# PhatStats_Slim_Enclosure_ESP_Lolin_D32_X.net
KiCad netlist of a schematic drawn in EAGLE
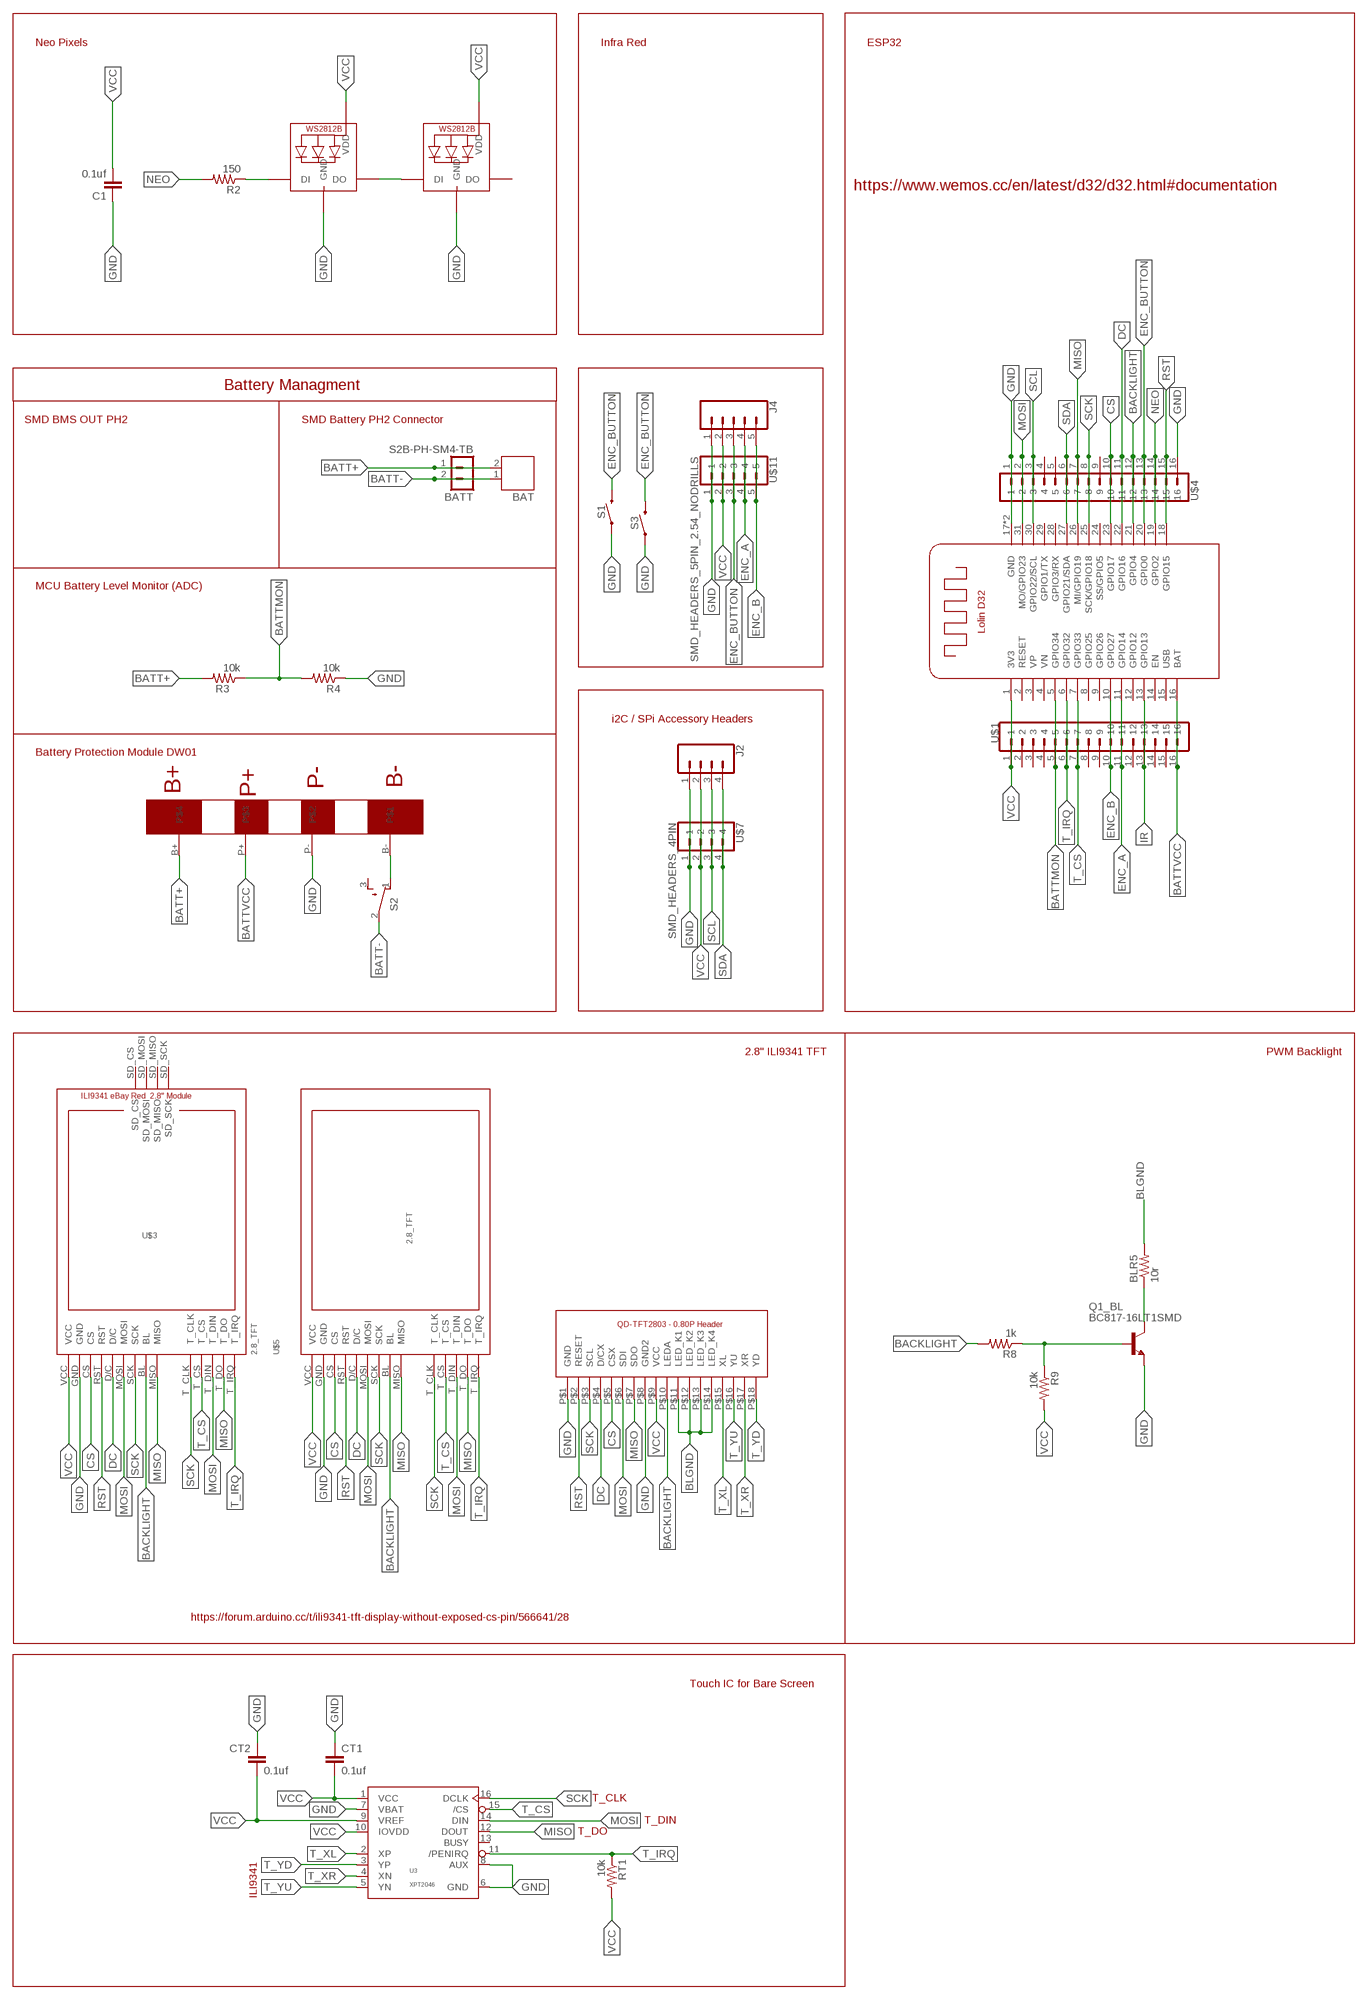
[diagram p0: schematic, sheet 1]

(export (version "E")
  (design (tool "Eeschema 10.0.6"))
  (components
    (comp (ref "0")
      (value "ILI9341-2.8")
      (footprint "eagle-import:ILI9341-2.8")
      (libsource (lib "eagle-import") (part "ILI9341-2.8"))
    )
    (comp (ref "BAT")
      (value "JST-PH2")
      (footprint "eagle-import:JST-PH2")
      (libsource (lib "eagle-import") (part "JST-PH2"))
    )
    (comp (ref "BATT")
      (value "S2B-PH-SM4-TB")
      (footprint "eagle-import:S2B-PH-SM4-TB")
      (libsource (lib "eagle-import") (part "S2B-PH-SM4-TB"))
    )
    (comp (ref "BLR5")
      (value "10r")
      (footprint "eagle-import:M1206")
      (libsource (lib "eagle-import") (part "R-US_M1206"))
    )
    (comp (ref "BMS")
      (value "DW01BATTERYPROT")
      (footprint "eagle-import:DW01BATTERYPROT")
      (libsource (lib "eagle-import") (part "DW01BATTERYPROT"))
    )
    (comp (ref "C1")
      (value "0.1uf")
      (footprint "eagle-import:C1206")
      (libsource (lib "eagle-import") (part "C-EUC1206"))
    )
    (comp (ref "CT1")
      (value "0.1uf")
      (footprint "eagle-import:C1206")
      (libsource (lib "eagle-import") (part "C-EUC1206"))
    )
    (comp (ref "CT2")
      (value "0.1uf")
      (footprint "eagle-import:C1206")
      (libsource (lib "eagle-import") (part "C-EUC1206"))
    )
    (comp (ref "J2")
      (value "CONN_04PTH")
      (footprint "eagle-import:1X04")
      (libsource (lib "eagle-import") (part "CONN_04PTH"))
    )
    (comp (ref "J4")
      (value "CONN_05")
      (footprint "eagle-import:1X05")
      (libsource (lib "eagle-import") (part "CONN_05"))
    )
    (comp (ref "NEO0")
      (value "WS2812B5050")
      (footprint "eagle-import:WS2812B")
      (libsource (lib "eagle-import") (part "WS2812B5050"))
    )
    (comp (ref "NEO1")
      (value "WS2812B5050")
      (footprint "eagle-import:WS2812B")
      (libsource (lib "eagle-import") (part "WS2812B5050"))
    )
    (comp (ref "Q1_BL")
      (value "BC817-16LT1SMD")
      (footprint "eagle-import:SOT23-BEC")
      (libsource (lib "eagle-import") (part "BC817SMD-16LT1"))
    )
    (comp (ref "R2")
      (value "150")
      (footprint "eagle-import:M1206")
      (libsource (lib "eagle-import") (part "R-US_M1206"))
    )
    (comp (ref "R3")
      (value "10k")
      (footprint "eagle-import:M1206")
      (libsource (lib "eagle-import") (part "R-US_M1206"))
    )
    (comp (ref "R4")
      (value "10k")
      (footprint "eagle-import:M1206")
      (libsource (lib "eagle-import") (part "R-US_M1206"))
    )
    (comp (ref "R8")
      (value "1k")
      (footprint "eagle-import:M1206")
      (libsource (lib "eagle-import") (part "R-US_M1206"))
    )
    (comp (ref "R9")
      (value "10k")
      (footprint "eagle-import:M1206")
      (libsource (lib "eagle-import") (part "R-US_M1206"))
    )
    (comp (ref "RT1")
      (value "10k")
      (footprint "eagle-import:M1206")
      (libsource (lib "eagle-import") (part "R-US_M1206"))
    )
    (comp (ref "S1")
      (value "MOMENTARY-SWITCH-SPST-PTH-6.0MM")
      (footprint "eagle-import:TACTILE_SWITCH_PTH_6.0MM")
      (libsource (lib "eagle-import") (part "MOMENTARY-SWITCH-SPST-PTH-6.0MM"))
    )
    (comp (ref "S2")
      (value "SK-12F14(1P2T)0.5A50VDC3MMPITCH")
      (footprint "eagle-import:SK-12F14(1P2T)0.5A50VDC3MMPITCH")
      (libsource (lib "eagle-import") (part "SK-12F14(1P2T)0.5A50VDC3MMPITCH"))
    )
    (comp (ref "S3")
      (value "MOMENTARY-SWITCH-SPST-SMD-6.2MM-TALL")
      (footprint "eagle-import:TACTILE_SWITCH_SMD_6.2MM_TALL")
      (libsource (lib "eagle-import") (part "MOMENTARY-SWITCH-SPST-SMD-6.2MM-TALL"))
    )
    (comp (ref "U$1")
      (value "SMD_HEADERS_16PIN_2.54_NODRILLSSMD_HEADERS_16PIN")
      (footprint "eagle-import:SMD_HEADERS_16PIN")
      (libsource (lib "eagle-import") (part "SMD_HEADERS_16PIN_2.54_NODRILLSSMD_HEADERS_16PIN"))
    )
    (comp (ref "U$2")
      (value "TML_LOLIND32")
      (footprint "eagle-import:TML_LOLIND32")
      (libsource (lib "eagle-import") (part "TML_LOLIND32"))
    )
    (comp (ref "U$3")
      (value "2.8_TFT")
      (footprint "eagle-import:2.8_TFT")
      (libsource (lib "eagle-import") (part "2.8_TFT"))
    )
    (comp (ref "U$4")
      (value "SMD_HEADERS_16PIN_2.54_NODRILLSSMD_HEADERS_16PIN")
      (footprint "eagle-import:SMD_HEADERS_16PIN")
      (libsource (lib "eagle-import") (part "SMD_HEADERS_16PIN_2.54_NODRILLSSMD_HEADERS_16PIN"))
    )
    (comp (ref "U$5")
      (value "2.8_TFT")
      (footprint "eagle-import:2.8_TFT")
      (libsource (lib "eagle-import") (part "TML_ili9341-2.8_tft-display_PinHeader only_2.8_TFT"))
    )
    (comp (ref "U$7")
      (value "SMD_HEADERS_4PIN")
      (footprint "eagle-import:SMD_HEADERS_4PIN")
      (libsource (lib "eagle-import") (part "SMD_HEADERS_4PIN"))
    )
    (comp (ref "U$11")
      (value "SMD_HEADERS_5PIN_2.54_NODRILLS")
      (footprint "eagle-import:SMD_HEADERS_5PIN")
      (libsource (lib "eagle-import") (part "SMD_HEADERS_5PIN_2.54_NODRILLS"))
    )
    (comp (ref "U3")
      (value "XPT2046")
      (footprint "eagle-import:TSSOP-16")
      (fields (field (name "MF") "Xptek"))
      (libsource (lib "eagle-import") (part "XPT2046"))
    )
  )
  (nets
    (net (code "1") (name "/USB") (class "Default")
      (node (ref "U$2") (pin "15") (pinfunction "USB_15") (pintype "power_in"))
    )
    (net (code "2") (name "BACKLIGHT") (class "Default")
      (node (ref "0") (pin "P$10") (pinfunction "LEDA_P$10") (pintype "bidirectional"))
      (node (ref "R8") (pin "2") (pinfunction "2_2") (pintype "passive"))
      (node (ref "U$2") (pin "21") (pinfunction "GPIO4_21") (pintype "bidirectional"))
      (node (ref "U$3") (pin "BL") (pinfunction "BL_BL") (pintype "bidirectional"))
      (node (ref "U$4") (pin "12") (pinfunction "12_12") (pintype "passive"))
      (node (ref "U$5") (pin "BL") (pinfunction "BL_BL") (pintype "bidirectional"))
    )
    (net (code "3") (name "BATT+") (class "Default")
      (node (ref "BAT") (pin "2") (pinfunction "2_2") (pintype "passive"))
      (node (ref "BATT") (pin "1") (pinfunction "1_1") (pintype "passive"))
      (node (ref "BMS") (pin "B+") (pinfunction "P$4_B+") (pintype "bidirectional"))
      (node (ref "R3") (pin "2") (pinfunction "2_2") (pintype "passive"))
    )
    (net (code "4") (name "BATT-") (class "Default")
      (node (ref "BAT") (pin "1") (pinfunction "1_1") (pintype "passive"))
      (node (ref "BATT") (pin "2") (pinfunction "2_2") (pintype "passive"))
      (node (ref "S2") (pin "2") (pinfunction "P_2") (pintype "passive"))
    )
    (net (code "5") (name "BATTMON") (class "Default")
      (node (ref "R3") (pin "1") (pinfunction "1_1") (pintype "passive"))
      (node (ref "R4") (pin "2") (pinfunction "2_2") (pintype "passive"))
      (node (ref "U$1") (pin "5") (pinfunction "5_5") (pintype "passive"))
      (node (ref "U$2") (pin "5") (pinfunction "GPIO34_5") (pintype "input"))
    )
    (net (code "6") (name "BATTVCC") (class "Default")
      (node (ref "BMS") (pin "P+") (pinfunction "P$3_P+") (pintype "bidirectional"))
      (node (ref "U$1") (pin "16") (pinfunction "16_16") (pintype "passive"))
      (node (ref "U$2") (pin "16") (pinfunction "BAT_16") (pintype "power_in"))
    )
    (net (code "7") (name "BLGND") (class "Default")
      (node (ref "0") (pin "P$11") (pinfunction "LED_K1_P$11") (pintype "bidirectional"))
      (node (ref "0") (pin "P$12") (pinfunction "LED_K2_P$12") (pintype "bidirectional"))
      (node (ref "0") (pin "P$13") (pinfunction "LED_K3_P$13") (pintype "bidirectional"))
      (node (ref "0") (pin "P$14") (pinfunction "LED_K4_P$14") (pintype "bidirectional"))
      (node (ref "BLR5") (pin "2") (pinfunction "2_2") (pintype "passive"))
    )
    (net (code "8") (name "CS") (class "Default")
      (node (ref "0") (pin "P$5") (pinfunction "CSX_P$5") (pintype "bidirectional"))
      (node (ref "U$2") (pin "23") (pinfunction "GPIO17_23") (pintype "bidirectional"))
      (node (ref "U$3") (pin "CS") (pinfunction "CS_CS") (pintype "bidirectional"))
      (node (ref "U$4") (pin "10") (pinfunction "10_10") (pintype "passive"))
      (node (ref "U$5") (pin "CS") (pinfunction "CS_CS") (pintype "bidirectional"))
    )
    (net (code "9") (name "DC") (class "Default")
      (node (ref "0") (pin "P$4") (pinfunction "D/CX_P$4") (pintype "bidirectional"))
      (node (ref "U$2") (pin "22") (pinfunction "GPIO16_22") (pintype "bidirectional"))
      (node (ref "U$3") (pin "D/C") (pinfunction "D/C_D/C") (pintype "bidirectional"))
      (node (ref "U$4") (pin "11") (pinfunction "11_11") (pintype "passive"))
      (node (ref "U$5") (pin "D/C") (pinfunction "D/C_D/C") (pintype "bidirectional"))
    )
    (net (code "10") (name "ENC_A") (class "Default")
      (node (ref "J4") (pin "4") (pinfunction "4_4") (pintype "passive"))
      (node (ref "U$1") (pin "11") (pinfunction "11_11") (pintype "passive"))
      (node (ref "U$11") (pin "4") (pinfunction "4_4") (pintype "passive"))
      (node (ref "U$2") (pin "11") (pinfunction "GPIO14_11") (pintype "bidirectional"))
    )
    (net (code "11") (name "ENC_B") (class "Default")
      (node (ref "J4") (pin "5") (pinfunction "5_5") (pintype "passive"))
      (node (ref "U$1") (pin "10") (pinfunction "10_10") (pintype "passive"))
      (node (ref "U$11") (pin "5") (pinfunction "5_5") (pintype "passive"))
      (node (ref "U$2") (pin "10") (pinfunction "GPIO27_10") (pintype "bidirectional"))
    )
    (net (code "12") (name "ENC_BUTTON") (class "Default")
      (node (ref "J4") (pin "3") (pinfunction "3_3") (pintype "passive"))
      (node (ref "S1") (pin "3") (pinfunction "2_3") (pintype "passive"))
      (node (ref "S3") (pin "B2") (pinfunction "2_B2") (pintype "passive"))
      (node (ref "U$11") (pin "3") (pinfunction "3_3") (pintype "passive"))
      (node (ref "U$2") (pin "20") (pinfunction "GPIO0_20") (pintype "bidirectional"))
      (node (ref "U$4") (pin "13") (pinfunction "13_13") (pintype "passive"))
    )
    (net (code "13") (name "GND") (class "Default")
      (node (ref "0") (pin "P$1") (pinfunction "GND_P$1") (pintype "bidirectional"))
      (node (ref "0") (pin "P$8") (pinfunction "GND2_P$8") (pintype "bidirectional"))
      (node (ref "BMS") (pin "P-") (pinfunction "P$2_P-") (pintype "bidirectional"))
      (node (ref "C1") (pin "1") (pinfunction "1_1") (pintype "passive"))
      (node (ref "CT1") (pin "1") (pinfunction "1_1") (pintype "passive"))
      (node (ref "CT2") (pin "1") (pinfunction "1_1") (pintype "passive"))
      (node (ref "J2") (pin "1") (pinfunction "1_1") (pintype "passive"))
      (node (ref "J4") (pin "1") (pinfunction "1_1") (pintype "passive"))
      (node (ref "NEO0") (pin "3-GND") (pinfunction "GND_3-GND") (pintype "power_in"))
      (node (ref "NEO1") (pin "3-GND") (pinfunction "GND_3-GND") (pintype "power_in"))
      (node (ref "Q1_BL") (pin "E") (pinfunction "E_E") (pintype "passive"))
      (node (ref "R4") (pin "1") (pinfunction "1_1") (pintype "passive"))
      (node (ref "S1") (pin "1") (pinfunction "1_1") (pintype "passive"))
      (node (ref "S3") (pin "A2") (pinfunction "1_A2") (pintype "passive"))
      (node (ref "U$11") (pin "1") (pinfunction "1_1") (pintype "passive"))
      (node (ref "U$2") (pin "17") (pinfunction "GND_17") (pintype "power_in"))
      (node (ref "U$2") (pin "32") (pinfunction "GND_32") (pintype "power_in"))
      (node (ref "U$3") (pin "GND") (pinfunction "GND_GND") (pintype "bidirectional"))
      (node (ref "U$4") (pin "1") (pinfunction "1_1") (pintype "passive"))
      (node (ref "U$4") (pin "16") (pinfunction "16_16") (pintype "passive"))
      (node (ref "U$5") (pin "GND") (pinfunction "GND_GND") (pintype "bidirectional"))
      (node (ref "U$7") (pin "1") (pinfunction "1_1") (pintype "passive"))
      (node (ref "U3") (pin "6") (pinfunction "GND_6") (pintype "power_in"))
      (node (ref "U3") (pin "7") (pinfunction "VBAT_7") (pintype "input"))
      (node (ref "U3") (pin "8") (pinfunction "AUX_8") (pintype "input"))
    )
    (net (code "14") (name "IR") (class "Default")
      (node (ref "U$1") (pin "13") (pinfunction "13_13") (pintype "passive"))
      (node (ref "U$2") (pin "13") (pinfunction "GPIO13_13") (pintype "bidirectional"))
    )
    (net (code "15") (name "MISO") (class "Default")
      (node (ref "0") (pin "P$7") (pinfunction "SDO_P$7") (pintype "bidirectional"))
      (node (ref "U$2") (pin "26") (pinfunction "MI/GPIO19_26") (pintype "bidirectional"))
      (node (ref "U$3") (pin "MISO") (pinfunction "MISO_MISO") (pintype "bidirectional"))
      (node (ref "U$3") (pin "T_DO") (pinfunction "T_DO_T_DO") (pintype "bidirectional"))
      (node (ref "U$4") (pin "7") (pinfunction "7_7") (pintype "passive"))
      (node (ref "U$5") (pin "MISO") (pinfunction "MISO_MISO") (pintype "bidirectional"))
      (node (ref "U$5") (pin "T_DO") (pinfunction "T_DO_T_DO") (pintype "bidirectional"))
      (node (ref "U3") (pin "12") (pinfunction "DOUT_12") (pintype "output"))
    )
    (net (code "16") (name "MOSI") (class "Default")
      (node (ref "0") (pin "P$6") (pinfunction "SDI_P$6") (pintype "bidirectional"))
      (node (ref "U$2") (pin "31") (pinfunction "MO/GPIO23_31") (pintype "bidirectional"))
      (node (ref "U$3") (pin "MOSI") (pinfunction "MOSI_MOSI") (pintype "bidirectional"))
      (node (ref "U$3") (pin "T_DIN") (pinfunction "T_DIN_T_DIN") (pintype "bidirectional"))
      (node (ref "U$4") (pin "2") (pinfunction "2_2") (pintype "passive"))
      (node (ref "U$5") (pin "MOSI") (pinfunction "MOSI_MOSI") (pintype "bidirectional"))
      (node (ref "U$5") (pin "T_DIN") (pinfunction "T_DIN_T_DIN") (pintype "bidirectional"))
      (node (ref "U3") (pin "14") (pinfunction "DIN_14") (pintype "input"))
    )
    (net (code "17") (name "NEO") (class "Default")
      (node (ref "R2") (pin "2") (pinfunction "2_2") (pintype "passive"))
      (node (ref "U$2") (pin "19") (pinfunction "GPIO2_19") (pintype "bidirectional"))
      (node (ref "U$4") (pin "14") (pinfunction "14_14") (pintype "passive"))
    )
    (net (code "18") (name "Net-(BLR5-Pad1)") (class "Default")
      (node (ref "BLR5") (pin "1") (pinfunction "1_1") (pintype "passive"))
      (node (ref "Q1_BL") (pin "C") (pinfunction "C_C") (pintype "passive"))
    )
    (net (code "19") (name "Net-(BMS-P$1)") (class "Default")
      (node (ref "BMS") (pin "B-") (pinfunction "P$1_B-") (pintype "bidirectional"))
      (node (ref "S2") (pin "1") (pinfunction "O_1") (pintype "passive"))
    )
    (net (code "20") (name "Net-(NEO0-DI)") (class "Default")
      (node (ref "NEO0") (pin "4-DIN") (pinfunction "DI_4-DIN") (pintype "input"))
      (node (ref "R2") (pin "1") (pinfunction "1_1") (pintype "passive"))
    )
    (net (code "21") (name "Net-(NEO0-DO)") (class "Default")
      (node (ref "NEO0") (pin "2-DOUT") (pinfunction "DO_2-DOUT") (pintype "output"))
      (node (ref "NEO1") (pin "4-DIN") (pinfunction "DI_4-DIN") (pintype "input"))
    )
    (net (code "22") (name "Net-(Q1_BL-PadB)") (class "Default")
      (node (ref "Q1_BL") (pin "B") (pinfunction "B_B") (pintype "passive"))
      (node (ref "R8") (pin "1") (pinfunction "1_1") (pintype "passive"))
      (node (ref "R9") (pin "1") (pinfunction "1_1") (pintype "passive"))
    )
    (net (code "23") (name "RST") (class "Default")
      (node (ref "0") (pin "P$2") (pinfunction "RESET_P$2") (pintype "bidirectional"))
      (node (ref "U$2") (pin "18") (pinfunction "GPIO15_18") (pintype "bidirectional"))
      (node (ref "U$3") (pin "RST") (pinfunction "RST_RST") (pintype "bidirectional"))
      (node (ref "U$4") (pin "15") (pinfunction "15_15") (pintype "passive"))
      (node (ref "U$5") (pin "RST") (pinfunction "RST_RST") (pintype "bidirectional"))
    )
    (net (code "24") (name "SCK") (class "Default")
      (node (ref "0") (pin "P$3") (pinfunction "SCL_P$3") (pintype "bidirectional"))
      (node (ref "U$2") (pin "25") (pinfunction "SCK/GPIO18_25") (pintype "bidirectional"))
      (node (ref "U$3") (pin "SCK") (pinfunction "SCK_SCK") (pintype "bidirectional"))
      (node (ref "U$3") (pin "T_CLK") (pinfunction "T_CLK_T_CLK") (pintype "bidirectional"))
      (node (ref "U$4") (pin "8") (pinfunction "8_8") (pintype "passive"))
      (node (ref "U$5") (pin "SCK") (pinfunction "SCK_SCK") (pintype "bidirectional"))
      (node (ref "U$5") (pin "T_CLK") (pinfunction "T_CLK_T_CLK") (pintype "bidirectional"))
      (node (ref "U3") (pin "16") (pinfunction "DCLK_16") (pintype "input"))
    )
    (net (code "25") (name "SCL") (class "Default")
      (node (ref "J2") (pin "3") (pinfunction "3_3") (pintype "passive"))
      (node (ref "U$2") (pin "30") (pinfunction "GPIO22/SCL_30") (pintype "bidirectional"))
      (node (ref "U$4") (pin "3") (pinfunction "3_3") (pintype "passive"))
      (node (ref "U$7") (pin "3") (pinfunction "3_3") (pintype "passive"))
    )
    (net (code "26") (name "SDA") (class "Default")
      (node (ref "J2") (pin "4") (pinfunction "4_4") (pintype "passive"))
      (node (ref "U$2") (pin "27") (pinfunction "GPIO21/SDA_27") (pintype "bidirectional"))
      (node (ref "U$4") (pin "6") (pinfunction "6_6") (pintype "passive"))
      (node (ref "U$7") (pin "4") (pinfunction "4_4") (pintype "passive"))
    )
    (net (code "27") (name "T_CS") (class "Default")
      (node (ref "U$1") (pin "7") (pinfunction "7_7") (pintype "passive"))
      (node (ref "U$2") (pin "7") (pinfunction "GPIO33_7") (pintype "bidirectional"))
      (node (ref "U$3") (pin "T_CS") (pinfunction "T_CS_T_CS") (pintype "bidirectional"))
      (node (ref "U$5") (pin "T_CS") (pinfunction "T_CS_T_CS") (pintype "bidirectional"))
      (node (ref "U3") (pin "15") (pinfunction "/CS_15") (pintype "input"))
    )
    (net (code "28") (name "T_IRQ") (class "Default")
      (node (ref "RT1") (pin "1") (pinfunction "1_1") (pintype "passive"))
      (node (ref "U$1") (pin "6") (pinfunction "6_6") (pintype "passive"))
      (node (ref "U$2") (pin "6") (pinfunction "GPIO32_6") (pintype "bidirectional"))
      (node (ref "U$3") (pin "T_IRQ") (pinfunction "T_IRQ_T_IRQ") (pintype "bidirectional"))
      (node (ref "U$5") (pin "T_IRQ") (pinfunction "T_IRQ_T_IRQ") (pintype "bidirectional"))
      (node (ref "U3") (pin "11") (pinfunction "/PENIRQ_11") (pintype "output"))
    )
    (net (code "29") (name "T_XL") (class "Default")
      (node (ref "0") (pin "P$15") (pinfunction "XL_P$15") (pintype "bidirectional"))
      (node (ref "U3") (pin "2") (pinfunction "XP_2") (pintype "input"))
    )
    (net (code "30") (name "T_XR") (class "Default")
      (node (ref "0") (pin "P$17") (pinfunction "XR_P$17") (pintype "bidirectional"))
      (node (ref "U3") (pin "4") (pinfunction "XN_4") (pintype "input"))
    )
    (net (code "31") (name "T_YD") (class "Default")
      (node (ref "0") (pin "P$18") (pinfunction "YD_P$18") (pintype "bidirectional"))
      (node (ref "U3") (pin "3") (pinfunction "YP_3") (pintype "input"))
    )
    (net (code "32") (name "T_YU") (class "Default")
      (node (ref "0") (pin "P$16") (pinfunction "YU_P$16") (pintype "bidirectional"))
      (node (ref "U3") (pin "5") (pinfunction "YN_5") (pintype "input"))
    )
    (net (code "33") (name "VCC") (class "Default")
      (node (ref "0") (pin "P$9") (pinfunction "VCC_P$9") (pintype "bidirectional"))
      (node (ref "C1") (pin "2") (pinfunction "2_2") (pintype "passive"))
      (node (ref "CT1") (pin "2") (pinfunction "2_2") (pintype "passive"))
      (node (ref "CT2") (pin "2") (pinfunction "2_2") (pintype "passive"))
      (node (ref "J2") (pin "2") (pinfunction "2_2") (pintype "passive"))
      (node (ref "J4") (pin "2") (pinfunction "2_2") (pintype "passive"))
      (node (ref "NEO0") (pin "1-VDD") (pinfunction "VDD_1-VDD") (pintype "power_in"))
      (node (ref "NEO1") (pin "1-VDD") (pinfunction "VDD_1-VDD") (pintype "power_in"))
      (node (ref "R9") (pin "2") (pinfunction "2_2") (pintype "passive"))
      (node (ref "RT1") (pin "2") (pinfunction "2_2") (pintype "passive"))
      (node (ref "U$1") (pin "1") (pinfunction "1_1") (pintype "passive"))
      (node (ref "U$11") (pin "2") (pinfunction "2_2") (pintype "passive"))
      (node (ref "U$2") (pin "1") (pinfunction "3V3_1") (pintype "power_in"))
      (node (ref "U$3") (pin "VCC") (pinfunction "VCC_VCC") (pintype "bidirectional"))
      (node (ref "U$5") (pin "VCC") (pinfunction "VCC_VCC") (pintype "bidirectional"))
      (node (ref "U$7") (pin "2") (pinfunction "2_2") (pintype "passive"))
      (node (ref "U3") (pin "1") (pinfunction "VCC_1") (pintype "power_in"))
      (node (ref "U3") (pin "10") (pinfunction "IOVDD_10") (pintype "power_in"))
      (node (ref "U3") (pin "9") (pinfunction "VREF_9") (pintype "input"))
    )
    (net (code "34") (name "unconnected-(NEO1-DO-Pad2-DOUT)") (class "Default")
      (node (ref "NEO1") (pin "2-DOUT") (pinfunction "DO_2-DOUT") (pintype "output"))
    )
    (net (code "35") (name "unconnected-(S2-S-Pad3)") (class "Default")
      (node (ref "S2") (pin "3") (pinfunction "S_3") (pintype "passive"))
    )
    (net (code "36") (name "unconnected-(U$1-Pad2)") (class "Default")
      (node (ref "U$1") (pin "2") (pinfunction "2_2") (pintype "passive"))
    )
    (net (code "37") (name "unconnected-(U$1-Pad3)") (class "Default")
      (node (ref "U$1") (pin "3") (pinfunction "3_3") (pintype "passive"))
    )
    (net (code "38") (name "unconnected-(U$1-Pad4)") (class "Default")
      (node (ref "U$1") (pin "4") (pinfunction "4_4") (pintype "passive"))
    )
    (net (code "39") (name "unconnected-(U$1-Pad8)") (class "Default")
      (node (ref "U$1") (pin "8") (pinfunction "8_8") (pintype "passive"))
    )
    (net (code "40") (name "unconnected-(U$1-Pad9)") (class "Default")
      (node (ref "U$1") (pin "9") (pinfunction "9_9") (pintype "passive"))
    )
    (net (code "41") (name "unconnected-(U$1-Pad12)") (class "Default")
      (node (ref "U$1") (pin "12") (pinfunction "12_12") (pintype "passive"))
    )
    (net (code "42") (name "unconnected-(U$1-Pad14)") (class "Default")
      (node (ref "U$1") (pin "14") (pinfunction "14_14") (pintype "passive"))
    )
    (net (code "43") (name "unconnected-(U$1-Pad15)") (class "Default")
      (node (ref "U$1") (pin "15") (pinfunction "15_15") (pintype "passive"))
    )
    (net (code "44") (name "unconnected-(U$2-EN-Pad14)") (class "Default")
      (node (ref "U$2") (pin "14") (pinfunction "EN_14") (pintype "input"))
    )
    (net (code "45") (name "unconnected-(U$2-GPIO1{slash}TX-Pad29)") (class "Default")
      (node (ref "U$2") (pin "29") (pinfunction "GPIO1/TX_29") (pintype "bidirectional"))
    )
    (net (code "46") (name "unconnected-(U$2-GPIO3{slash}RX-Pad28)") (class "Default")
      (node (ref "U$2") (pin "28") (pinfunction "GPIO3/RX_28") (pintype "bidirectional"))
    )
    (net (code "47") (name "unconnected-(U$2-GPIO12-Pad12)") (class "Default")
      (node (ref "U$2") (pin "12") (pinfunction "GPIO12_12") (pintype "bidirectional"))
    )
    (net (code "48") (name "unconnected-(U$2-GPIO25-Pad8)") (class "Default")
      (node (ref "U$2") (pin "8") (pinfunction "GPIO25_8") (pintype "bidirectional"))
    )
    (net (code "49") (name "unconnected-(U$2-GPIO26-Pad9)") (class "Default")
      (node (ref "U$2") (pin "9") (pinfunction "GPIO26_9") (pintype "bidirectional"))
    )
    (net (code "50") (name "unconnected-(U$2-RESET-Pad2)") (class "Default")
      (node (ref "U$2") (pin "2") (pinfunction "RESET_2") (pintype "input"))
    )
    (net (code "51") (name "unconnected-(U$2-SS{slash}GPIO5-Pad24)") (class "Default")
      (node (ref "U$2") (pin "24") (pinfunction "SS/GPIO5_24") (pintype "bidirectional"))
    )
    (net (code "52") (name "unconnected-(U$2-VN-Pad4)") (class "Default")
      (node (ref "U$2") (pin "4") (pinfunction "VN_4") (pintype "no_connect"))
    )
    (net (code "53") (name "unconnected-(U$2-VP-Pad3)") (class "Default")
      (node (ref "U$2") (pin "3") (pinfunction "VP_3") (pintype "no_connect"))
    )
    (net (code "54") (name "unconnected-(U$3-PadSD_CS)") (class "Default")
      (node (ref "U$3") (pin "SD_CS") (pinfunction "SD_CS_SD_CS") (pintype "bidirectional"))
    )
    (net (code "55") (name "unconnected-(U$3-PadSD_MISO)") (class "Default")
      (node (ref "U$3") (pin "SD_MISO") (pinfunction "SD_MISO_SD_MISO") (pintype "bidirectional"))
    )
    (net (code "56") (name "unconnected-(U$3-PadSD_MOSI)") (class "Default")
      (node (ref "U$3") (pin "SD_MOSI") (pinfunction "SD_MOSI_SD_MOSI") (pintype "bidirectional"))
    )
    (net (code "57") (name "unconnected-(U$3-PadSD_SCK)") (class "Default")
      (node (ref "U$3") (pin "SD_SCK") (pinfunction "SD_SCK_SD_SCK") (pintype "bidirectional"))
    )
    (net (code "58") (name "unconnected-(U$4-Pad4)") (class "Default")
      (node (ref "U$4") (pin "4") (pinfunction "4_4") (pintype "passive"))
    )
    (net (code "59") (name "unconnected-(U$4-Pad5)") (class "Default")
      (node (ref "U$4") (pin "5") (pinfunction "5_5") (pintype "passive"))
    )
    (net (code "60") (name "unconnected-(U$4-Pad9)") (class "Default")
      (node (ref "U$4") (pin "9") (pinfunction "9_9") (pintype "passive"))
    )
    (net (code "61") (name "unconnected-(U3-BUSY-Pad13)") (class "Default")
      (node (ref "U3") (pin "13") (pinfunction "BUSY_13") (pintype "output"))
    )
  )
)
